# businessCard.net
KiCad netlist of a schematic drawn in EAGLE
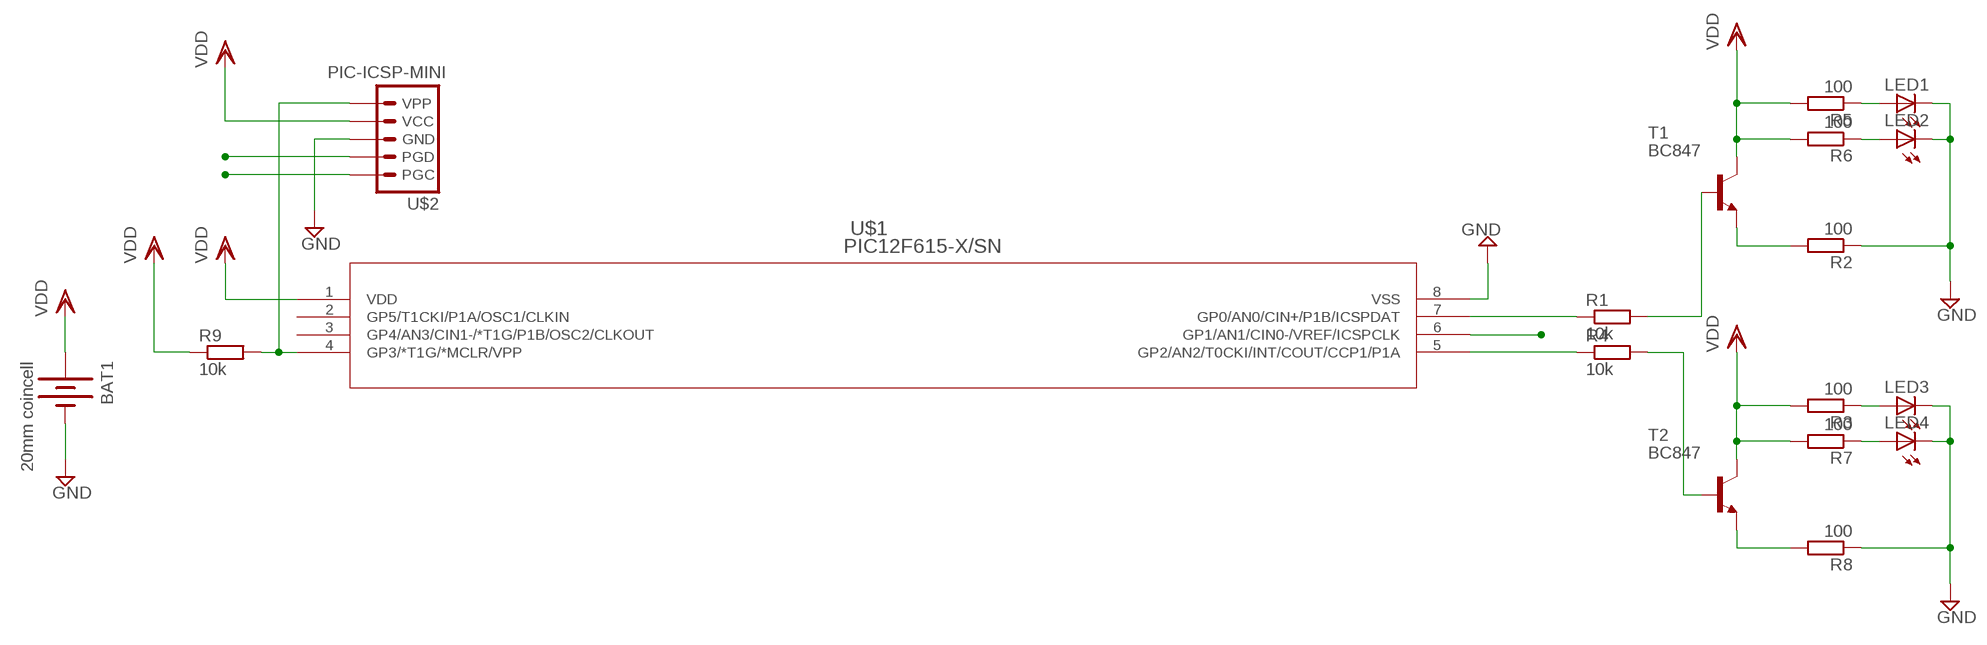
[diagram p0: schematic, sheet 1]

(export (version "E")
  (design (tool "Eeschema 10.0.6"))
  (components
    (comp (ref "BAT1")
      (value "20mm coincell")
      (footprint "eagle-import:BATTCON_20MM_4LEGS")
      (libsource (lib "eagle-import") (part "BATTERY20MM_4LEGS"))
    )
    (comp (ref "LED1")
      (value "LEDCHIPLED_0805")
      (footprint "eagle-import:CHIPLED_0805")
      (libsource (lib "eagle-import") (part "LEDCHIPLED_0805"))
    )
    (comp (ref "LED2")
      (value "LEDCHIPLED_0805")
      (footprint "eagle-import:CHIPLED_0805")
      (libsource (lib "eagle-import") (part "LEDCHIPLED_0805"))
    )
    (comp (ref "LED3")
      (value "LEDCHIPLED_0805")
      (footprint "eagle-import:CHIPLED_0805")
      (libsource (lib "eagle-import") (part "LEDCHIPLED_0805"))
    )
    (comp (ref "LED4")
      (value "LEDCHIPLED_0805")
      (footprint "eagle-import:CHIPLED_0805")
      (libsource (lib "eagle-import") (part "LEDCHIPLED_0805"))
    )
    (comp (ref "R1")
      (value "10k")
      (footprint "eagle-import:R0805")
      (libsource (lib "eagle-import") (part "R-EU_R0805"))
    )
    (comp (ref "R2")
      (value "100")
      (footprint "eagle-import:R0805")
      (libsource (lib "eagle-import") (part "R-EU_R0805"))
    )
    (comp (ref "R3")
      (value "100")
      (footprint "eagle-import:R0805")
      (libsource (lib "eagle-import") (part "R-EU_R0805"))
    )
    (comp (ref "R4")
      (value "10k")
      (footprint "eagle-import:R0805")
      (libsource (lib "eagle-import") (part "R-EU_R0805"))
    )
    (comp (ref "R5")
      (value "100")
      (footprint "eagle-import:R0805")
      (libsource (lib "eagle-import") (part "R-EU_R0805"))
    )
    (comp (ref "R6")
      (value "100")
      (footprint "eagle-import:R0805")
      (libsource (lib "eagle-import") (part "R-EU_R0805"))
    )
    (comp (ref "R7")
      (value "100")
      (footprint "eagle-import:R0805")
      (libsource (lib "eagle-import") (part "R-EU_R0805"))
    )
    (comp (ref "R8")
      (value "100")
      (footprint "eagle-import:R0805")
      (libsource (lib "eagle-import") (part "R-EU_R0805"))
    )
    (comp (ref "R9")
      (value "10k")
      (footprint "eagle-import:R0805")
      (libsource (lib "eagle-import") (part "R-EU_R0805"))
    )
    (comp (ref "T1")
      (value "BC847")
      (footprint "eagle-import:SOT23")
      (libsource (lib "eagle-import") (part "BC847"))
    )
    (comp (ref "T2")
      (value "BC847")
      (footprint "eagle-import:SOT23")
      (libsource (lib "eagle-import") (part "BC847"))
    )
    (comp (ref "U$1")
      (value "PIC12F615-X/SN")
      (footprint "eagle-import:SOIC8-N_MC")
      (libsource (lib "eagle-import") (part "PIC12F615-X/SN"))
    )
    (comp (ref "U$2")
      (value "PIC-ICSP-MINI")
      (footprint "eagle-import:PIC-ICSP-MINI")
      (libsource (lib "eagle-import") (part "PIC-ICSP-MINI"))
    )
  )
  (nets
    (net (code "1") (name "/ICSPCLK") (class "Default")
      (node (ref "U$1") (pin "6") (pinfunction "GP1/AN1/CIN0-/VREF/ICSPCLK_6") (pintype "passive"))
      (node (ref "U$2") (pin "5") (pinfunction "PGC_5") (pintype "passive"))
    )
    (net (code "2") (name "/ICSPDAT") (class "Default")
      (node (ref "R1") (pin "1") (pinfunction "1_1") (pintype "passive"))
      (node (ref "U$1") (pin "7") (pinfunction "GP0/AN0/CIN+/P1B/ICSPDAT_7") (pintype "passive"))
      (node (ref "U$2") (pin "4") (pinfunction "PGD_4") (pintype "passive"))
    )
    (net (code "3") (name "GND") (class "Default")
      (node (ref "BAT1") (pin "2") (pinfunction "-_2") (pintype "power_in"))
      (node (ref "LED1") (pin "C") (pinfunction "C_C") (pintype "passive"))
      (node (ref "LED2") (pin "C") (pinfunction "C_C") (pintype "passive"))
      (node (ref "LED3") (pin "C") (pinfunction "C_C") (pintype "passive"))
      (node (ref "LED4") (pin "C") (pinfunction "C_C") (pintype "passive"))
      (node (ref "R2") (pin "1") (pinfunction "1_1") (pintype "passive"))
      (node (ref "R8") (pin "1") (pinfunction "1_1") (pintype "passive"))
      (node (ref "U$1") (pin "8") (pinfunction "VSS_8") (pintype "passive"))
      (node (ref "U$2") (pin "3") (pinfunction "GND_3") (pintype "passive"))
    )
    (net (code "4") (name "Net-(LED1-PadA)") (class "Default")
      (node (ref "LED1") (pin "A") (pinfunction "A_A") (pintype "passive"))
      (node (ref "R5") (pin "1") (pinfunction "1_1") (pintype "passive"))
    )
    (net (code "5") (name "Net-(LED2-PadA)") (class "Default")
      (node (ref "LED2") (pin "A") (pinfunction "A_A") (pintype "passive"))
      (node (ref "R6") (pin "1") (pinfunction "1_1") (pintype "passive"))
    )
    (net (code "6") (name "Net-(LED3-PadA)") (class "Default")
      (node (ref "LED3") (pin "A") (pinfunction "A_A") (pintype "passive"))
      (node (ref "R3") (pin "1") (pinfunction "1_1") (pintype "passive"))
    )
    (net (code "7") (name "Net-(LED4-PadA)") (class "Default")
      (node (ref "LED4") (pin "A") (pinfunction "A_A") (pintype "passive"))
      (node (ref "R7") (pin "1") (pinfunction "1_1") (pintype "passive"))
    )
    (net (code "8") (name "Net-(T1-B)") (class "Default")
      (node (ref "R1") (pin "2") (pinfunction "2_2") (pintype "passive"))
      (node (ref "T1") (pin "1") (pinfunction "B_1") (pintype "passive"))
    )
    (net (code "9") (name "Net-(T1-E)") (class "Default")
      (node (ref "R2") (pin "2") (pinfunction "2_2") (pintype "passive"))
      (node (ref "T1") (pin "2") (pinfunction "E_2") (pintype "passive"))
    )
    (net (code "10") (name "Net-(T2-B)") (class "Default")
      (node (ref "R4") (pin "2") (pinfunction "2_2") (pintype "passive"))
      (node (ref "T2") (pin "1") (pinfunction "B_1") (pintype "passive"))
    )
    (net (code "11") (name "Net-(T2-E)") (class "Default")
      (node (ref "R8") (pin "2") (pinfunction "2_2") (pintype "passive"))
      (node (ref "T2") (pin "2") (pinfunction "E_2") (pintype "passive"))
    )
    (net (code "12") (name "Net-(U$1-GP2{slash}AN2{slash}T0CKI{slash}INT{slash}COUT{slash}CCP1{slash}P1A)") (class "Default")
      (node (ref "R4") (pin "1") (pinfunction "1_1") (pintype "passive"))
      (node (ref "U$1") (pin "5") (pinfunction "GP2/AN2/T0CKI/INT/COUT/CCP1/P1A_5") (pintype "passive"))
    )
    (net (code "13") (name "Net-(U$1-GP3{slash}*T1G{slash}*MCLR{slash}VPP)") (class "Default")
      (node (ref "R9") (pin "2") (pinfunction "2_2") (pintype "passive"))
      (node (ref "U$1") (pin "4") (pinfunction "GP3/*T1G/*MCLR/VPP_4") (pintype "passive"))
      (node (ref "U$2") (pin "1") (pinfunction "VPP_1") (pintype "passive"))
    )
    (net (code "14") (name "VDD") (class "Default")
      (node (ref "BAT1") (pin "1") (pinfunction "+_1") (pintype "power_in"))
      (node (ref "R3") (pin "2") (pinfunction "2_2") (pintype "passive"))
      (node (ref "R5") (pin "2") (pinfunction "2_2") (pintype "passive"))
      (node (ref "R6") (pin "2") (pinfunction "2_2") (pintype "passive"))
      (node (ref "R7") (pin "2") (pinfunction "2_2") (pintype "passive"))
      (node (ref "R9") (pin "1") (pinfunction "1_1") (pintype "passive"))
      (node (ref "T1") (pin "3") (pinfunction "C_3") (pintype "passive"))
      (node (ref "T2") (pin "3") (pinfunction "C_3") (pintype "passive"))
      (node (ref "U$1") (pin "1") (pinfunction "VDD_1") (pintype "passive"))
      (node (ref "U$2") (pin "2") (pinfunction "VCC_2") (pintype "passive"))
    )
    (net (code "15") (name "unconnected-(U$1-GP4{slash}AN3{slash}CIN1-{slash}*T1G{slash}P1B{slash}OSC2{slash}CLKOUT-Pad3)") (class "Default")
      (node (ref "U$1") (pin "3") (pinfunction "GP4/AN3/CIN1-/*T1G/P1B/OSC2/CLKOUT_3") (pintype "passive"))
    )
    (net (code "16") (name "unconnected-(U$1-GP5{slash}T1CKI{slash}P1A{slash}OSC1{slash}CLKIN-Pad2)") (class "Default")
      (node (ref "U$1") (pin "2") (pinfunction "GP5/T1CKI/P1A/OSC1/CLKIN_2") (pintype "passive"))
    )
  )
)
